# Coolrunner_IO.net
KiCad netlist of a schematic drawn in Altium Designer
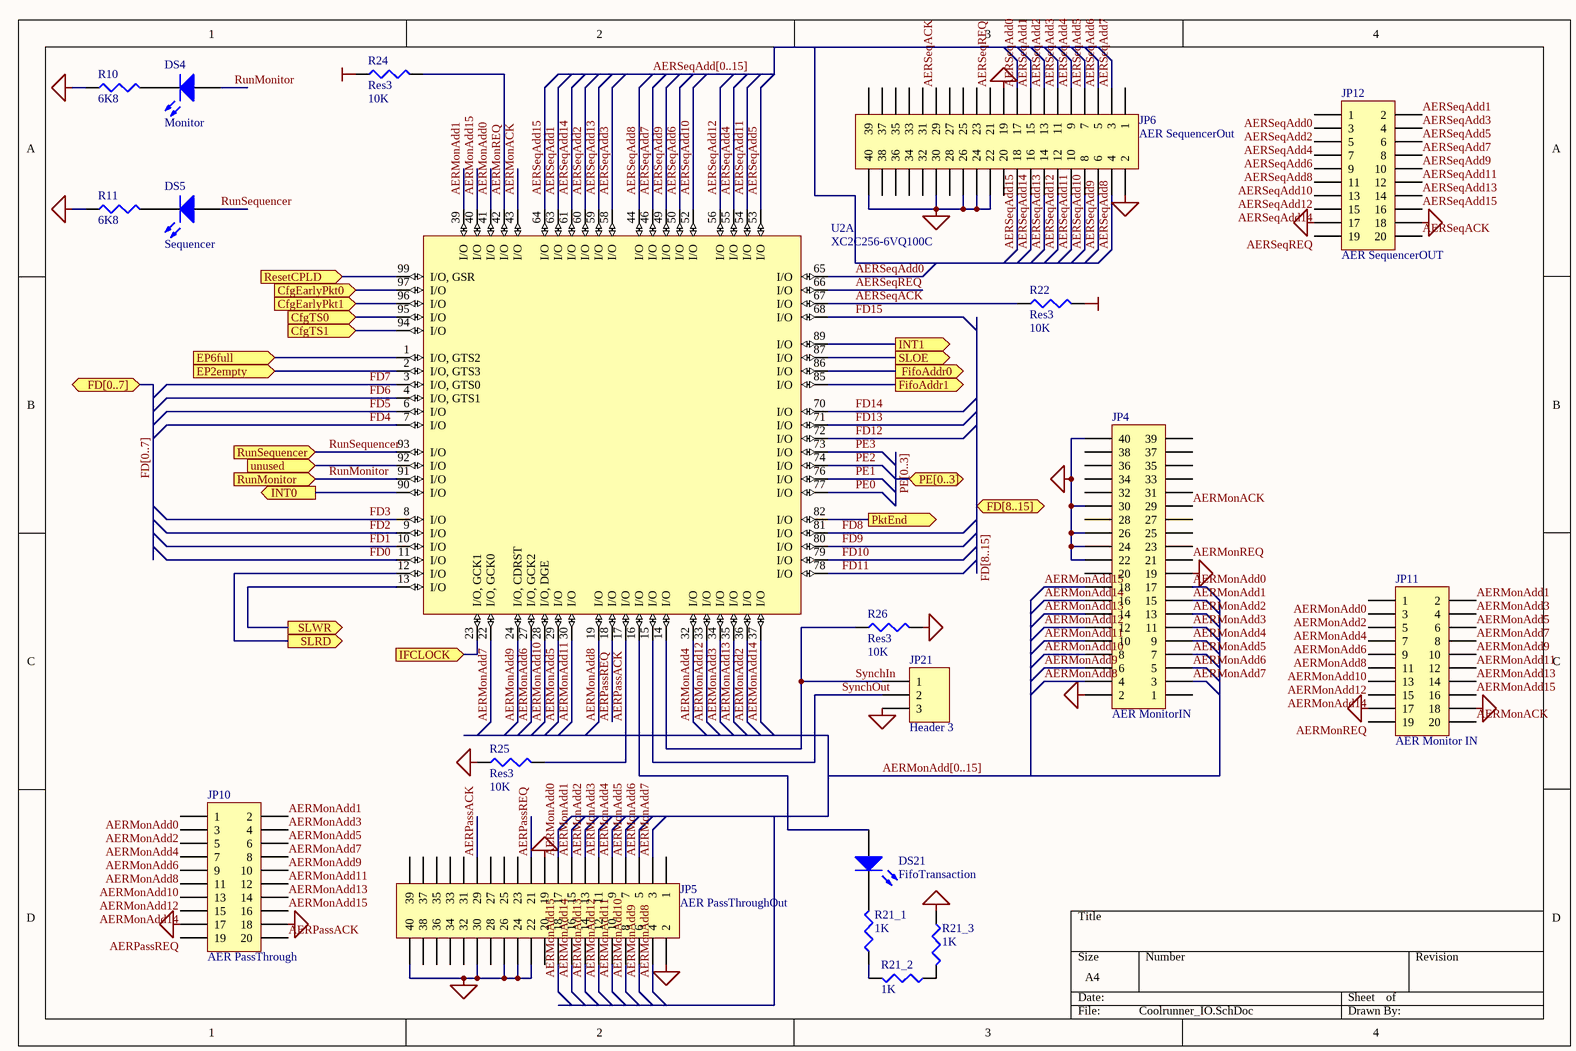
[diagram p0: Coolrunner_IO.SchDoc]

(export (version "E")
  (design (tool "Eeschema 10.0.6"))
  (components
    (comp (ref "DS4")
      (value "Monitor")
      (footprint "LED")
      (description "Typical RED, GREEN, YELLOW, AMBER GaAs LED")
      (fields (field (name "PUBLISHER") "Altium Limited"))
      (libsource (lib "Miscellaneous Devices") (part "LED2"))
    )
    (comp (ref "DS5")
      (value "Sequencer")
      (footprint "LED")
      (description "Typical RED, GREEN, YELLOW, AMBER GaAs LED")
      (fields (field (name "PUBLISHER") "Altium Limited"))
      (libsource (lib "Miscellaneous Devices") (part "LED2"))
    )
    (comp (ref "DS21")
      (value "FifoTransaction")
      (footprint "LED")
      (description "Typical RED, GREEN, YELLOW, AMBER GaAs LED")
      (fields (field (name "PUBLISHER") "Altium Limited"))
      (libsource (lib "Miscellaneous Devices") (part "LED2"))
    )
    (comp (ref "JP4")
      (value "AER MonitorIN")
      (footprint "IDC-40")
      (description "Header, 20-Pin, Dual row")
      (fields (field (name "PUBLISHER") "Altium Limited"))
      (libsource (lib "Miscellaneous Connectors") (part "MHDR2X20"))
    )
    (comp (ref "JP5")
      (value "AER PassThroughOut")
      (footprint "IDC-40")
      (description "Header, 20-Pin, Dual row")
      (fields (field (name "PUBLISHER") "Altium Limited"))
      (libsource (lib "") (part "MHDR2X20_1"))
    )
    (comp (ref "JP6")
      (value "AER SequencerOut")
      (footprint "IDC-40")
      (description "Header, 20-Pin, Dual row")
      (fields (field (name "PUBLISHER") "Altium Limited"))
      (libsource (lib "") (part "MHDR2X20_1"))
    )
    (comp (ref "JP10")
      (value "AER PassThrough")
      (footprint "HDR10x2 w/clips")
      (description "Header, 10-Pin, Dual row")
      (fields (field (name "PUBLISHER") "Altium Limited"))
      (libsource (lib "Miscellaneous Connectors") (part "Header 10X2"))
    )
    (comp (ref "JP11")
      (value "AER Monitor IN")
      (footprint "HDR10x2 w/clips")
      (description "Header, 10-Pin, Dual row")
      (fields (field (name "PUBLISHER") "Altium Limited"))
      (libsource (lib "Miscellaneous Connectors") (part "Header 10X2"))
    )
    (comp (ref "JP12")
      (value "AER SequencerOUT")
      (footprint "HDR10x2 w/clips")
      (description "Header, 10-Pin, Dual row")
      (fields (field (name "PUBLISHER") "Altium Limited"))
      (libsource (lib "Miscellaneous Connectors") (part "Header 10X2"))
    )
    (comp (ref "JP21")
      (value "Header 3")
      (footprint "HDR1X3")
      (description "Header, 3-Pin")
      (fields (field (name "PUBLISHER") "Altium Limited"))
      (libsource (lib "Miscellaneous Connectors") (part "Header 3"))
    )
    (comp (ref "R10")
      (value "6K8")
      (footprint "C1608-0603")
      (description "Resistor")
      (fields (field (name "Comment") "Res3") (field (name "PUBLISHER") "Altium Limited"))
      (libsource (lib "Miscellaneous Devices") (part "Res3"))
    )
    (comp (ref "R11")
      (value "6K8")
      (footprint "C1608-0603")
      (description "Resistor")
      (fields (field (name "Comment") "Res3") (field (name "PUBLISHER") "Altium Limited"))
      (libsource (lib "Miscellaneous Devices") (part "Res3"))
    )
    (comp (ref "R21_1")
      (value "1K")
      (footprint "C1608-0603")
      (description "Resistor")
      (fields (field (name "Comment") "Res3") (field (name "PUBLISHER") "Altium Limited"))
      (libsource (lib "Miscellaneous Devices") (part "Res3"))
    )
    (comp (ref "R21_2")
      (value "1K")
      (footprint "C1608-0603")
      (description "Resistor")
      (fields (field (name "Comment") "Res3") (field (name "PUBLISHER") "Altium Limited"))
      (libsource (lib "Miscellaneous Devices") (part "Res3"))
    )
    (comp (ref "R21_3")
      (value "1K")
      (footprint "C1608-0603")
      (description "Resistor")
      (fields (field (name "Comment") "Res3") (field (name "PUBLISHER") "Altium Limited"))
      (libsource (lib "Miscellaneous Devices") (part "Res3"))
    )
    (comp (ref "R22")
      (value "Res3")
      (footprint "C1608-0603")
      (description "Resistor")
      (fields (field (name "ALTIUM_VALUE") "10K") (field (name "PUBLISHER") "Altium Limited"))
      (libsource (lib "Miscellaneous Devices") (part "Res3"))
    )
    (comp (ref "R24")
      (value "Res3")
      (footprint "C1608-0603")
      (description "Resistor")
      (fields (field (name "ALTIUM_VALUE") "10K") (field (name "PUBLISHER") "Altium Limited"))
      (libsource (lib "Miscellaneous Devices") (part "Res3"))
    )
    (comp (ref "R25")
      (value "Res3")
      (footprint "C1608-0603")
      (description "Resistor")
      (fields (field (name "ALTIUM_VALUE") "10K") (field (name "PUBLISHER") "Altium Limited"))
      (libsource (lib "Miscellaneous Devices") (part "Res3"))
    )
    (comp (ref "R26")
      (value "Res3")
      (footprint "C1608-0603")
      (description "Resistor")
      (fields (field (name "ALTIUM_VALUE") "10K") (field (name "PUBLISHER") "Altium Limited"))
      (libsource (lib "Miscellaneous Devices") (part "Res3"))
    )
    (comp (ref "U2")
      (value "XC2C256-6VQ100C")
      (footprint "VQ100")
      (description "CoolRunner-II, 1.8V, 256 Macrocell CPLD, 100-Pin VQFP, Commercial Grade")
      (fields (field (name "PUBLISHER") "Altium Limited"))
      (libsource (lib "Xilinx CoolRunner II") (part "XC2C256-6VQ100C"))
    )
  )
  (nets
    (net (code "1") (name "/AERMonACK") (class "Default")
      (node (ref "JP11") (pin "20") (pinfunction "20_20") (pintype "passive"))
      (node (ref "JP4") (pin "29") (pinfunction "29_29") (pintype "passive"))
      (node (ref "U2") (pin "43") (pinfunction "I/O_43") (pintype "bidirectional"))
    )
    (net (code "2") (name "/AERMonAdd0") (class "Default")
      (node (ref "JP10") (pin "1") (pinfunction "1_1") (pintype "passive"))
      (node (ref "JP11") (pin "1") (pinfunction "1_1") (pintype "passive"))
      (node (ref "JP4") (pin "17") (pinfunction "17_17") (pintype "passive"))
      (node (ref "JP5") (pin "17") (pinfunction "17_17") (pintype "passive"))
      (node (ref "U2") (pin "41") (pinfunction "I/O_41") (pintype "bidirectional"))
    )
    (net (code "3") (name "/AERMonAdd1") (class "Default")
      (node (ref "JP10") (pin "2") (pinfunction "2_2") (pintype "passive"))
      (node (ref "JP11") (pin "2") (pinfunction "2_2") (pintype "passive"))
      (node (ref "JP4") (pin "15") (pinfunction "15_15") (pintype "passive"))
      (node (ref "JP5") (pin "15") (pinfunction "15_15") (pintype "passive"))
      (node (ref "U2") (pin "39") (pinfunction "I/O_39") (pintype "bidirectional"))
    )
    (net (code "4") (name "/AERMonAdd2") (class "Default")
      (node (ref "JP10") (pin "3") (pinfunction "3_3") (pintype "passive"))
      (node (ref "JP11") (pin "3") (pinfunction "3_3") (pintype "passive"))
      (node (ref "JP4") (pin "13") (pinfunction "13_13") (pintype "passive"))
      (node (ref "JP5") (pin "13") (pinfunction "13_13") (pintype "passive"))
      (node (ref "U2") (pin "36") (pinfunction "I/O_36") (pintype "bidirectional"))
    )
    (net (code "5") (name "/AERMonAdd3") (class "Default")
      (node (ref "JP10") (pin "4") (pinfunction "4_4") (pintype "passive"))
      (node (ref "JP11") (pin "4") (pinfunction "4_4") (pintype "passive"))
      (node (ref "JP4") (pin "11") (pinfunction "11_11") (pintype "passive"))
      (node (ref "JP5") (pin "11") (pinfunction "11_11") (pintype "passive"))
      (node (ref "U2") (pin "34") (pinfunction "I/O_34") (pintype "bidirectional"))
    )
    (net (code "6") (name "/AERMonAdd4") (class "Default")
      (node (ref "JP10") (pin "5") (pinfunction "5_5") (pintype "passive"))
      (node (ref "JP11") (pin "5") (pinfunction "5_5") (pintype "passive"))
      (node (ref "JP4") (pin "9") (pinfunction "9_9") (pintype "passive"))
      (node (ref "JP5") (pin "9") (pinfunction "9_9") (pintype "passive"))
      (node (ref "U2") (pin "32") (pinfunction "I/O_32") (pintype "bidirectional"))
    )
    (net (code "7") (name "/AERMonAdd5") (class "Default")
      (node (ref "JP10") (pin "6") (pinfunction "6_6") (pintype "passive"))
      (node (ref "JP11") (pin "6") (pinfunction "6_6") (pintype "passive"))
      (node (ref "JP4") (pin "7") (pinfunction "7_7") (pintype "passive"))
      (node (ref "JP5") (pin "7") (pinfunction "7_7") (pintype "passive"))
      (node (ref "U2") (pin "29") (pinfunction "I/O_29") (pintype "bidirectional"))
    )
    (net (code "8") (name "/AERMonAdd6") (class "Default")
      (node (ref "JP10") (pin "7") (pinfunction "7_7") (pintype "passive"))
      (node (ref "JP11") (pin "7") (pinfunction "7_7") (pintype "passive"))
      (node (ref "JP4") (pin "5") (pinfunction "5_5") (pintype "passive"))
      (node (ref "JP5") (pin "5") (pinfunction "5_5") (pintype "passive"))
      (node (ref "U2") (pin "27") (pinfunction "I/O,_GCK2_27") (pintype "bidirectional"))
    )
    (net (code "9") (name "/AERMonAdd7") (class "Default")
      (node (ref "JP10") (pin "8") (pinfunction "8_8") (pintype "passive"))
      (node (ref "JP11") (pin "8") (pinfunction "8_8") (pintype "passive"))
      (node (ref "JP4") (pin "3") (pinfunction "3_3") (pintype "passive"))
      (node (ref "JP5") (pin "3") (pinfunction "3_3") (pintype "passive"))
      (node (ref "U2") (pin "22") (pinfunction "I/O,_GCK0_22") (pintype "bidirectional"))
    )
    (net (code "10") (name "/AERMonAdd8") (class "Default")
      (node (ref "JP10") (pin "9") (pinfunction "9_9") (pintype "passive"))
      (node (ref "JP11") (pin "9") (pinfunction "9_9") (pintype "passive"))
      (node (ref "JP4") (pin "4") (pinfunction "4_4") (pintype "passive"))
      (node (ref "JP5") (pin "4") (pinfunction "4_4") (pintype "passive"))
      (node (ref "U2") (pin "19") (pinfunction "I/O_19") (pintype "bidirectional"))
    )
    (net (code "11") (name "/AERMonAdd9") (class "Default")
      (node (ref "JP10") (pin "10") (pinfunction "10_10") (pintype "passive"))
      (node (ref "JP11") (pin "10") (pinfunction "10_10") (pintype "passive"))
      (node (ref "JP4") (pin "6") (pinfunction "6_6") (pintype "passive"))
      (node (ref "JP5") (pin "6") (pinfunction "6_6") (pintype "passive"))
      (node (ref "U2") (pin "24") (pinfunction "I/O,_CDRST_24") (pintype "bidirectional"))
    )
    (net (code "12") (name "/AERMonAdd10") (class "Default")
      (node (ref "JP10") (pin "11") (pinfunction "11_11") (pintype "passive"))
      (node (ref "JP11") (pin "11") (pinfunction "11_11") (pintype "passive"))
      (node (ref "JP4") (pin "8") (pinfunction "8_8") (pintype "passive"))
      (node (ref "JP5") (pin "8") (pinfunction "8_8") (pintype "passive"))
      (node (ref "U2") (pin "28") (pinfunction "I/O,_DGE_28") (pintype "bidirectional"))
    )
    (net (code "13") (name "/AERMonAdd11") (class "Default")
      (node (ref "JP10") (pin "12") (pinfunction "12_12") (pintype "passive"))
      (node (ref "JP11") (pin "12") (pinfunction "12_12") (pintype "passive"))
      (node (ref "JP4") (pin "10") (pinfunction "10_10") (pintype "passive"))
      (node (ref "JP5") (pin "10") (pinfunction "10_10") (pintype "passive"))
      (node (ref "U2") (pin "30") (pinfunction "I/O_30") (pintype "bidirectional"))
    )
    (net (code "14") (name "/AERMonAdd12") (class "Default")
      (node (ref "JP10") (pin "13") (pinfunction "13_13") (pintype "passive"))
      (node (ref "JP11") (pin "13") (pinfunction "13_13") (pintype "passive"))
      (node (ref "JP4") (pin "12") (pinfunction "12_12") (pintype "passive"))
      (node (ref "JP5") (pin "12") (pinfunction "12_12") (pintype "passive"))
      (node (ref "U2") (pin "33") (pinfunction "I/O_33") (pintype "bidirectional"))
    )
    (net (code "15") (name "/AERMonAdd13") (class "Default")
      (node (ref "JP10") (pin "14") (pinfunction "14_14") (pintype "passive"))
      (node (ref "JP11") (pin "14") (pinfunction "14_14") (pintype "passive"))
      (node (ref "JP4") (pin "14") (pinfunction "14_14") (pintype "passive"))
      (node (ref "JP5") (pin "14") (pinfunction "14_14") (pintype "passive"))
      (node (ref "U2") (pin "35") (pinfunction "I/O_35") (pintype "bidirectional"))
    )
    (net (code "16") (name "/AERMonAdd14") (class "Default")
      (node (ref "JP10") (pin "15") (pinfunction "15_15") (pintype "passive"))
      (node (ref "JP11") (pin "15") (pinfunction "15_15") (pintype "passive"))
      (node (ref "JP4") (pin "16") (pinfunction "16_16") (pintype "passive"))
      (node (ref "JP5") (pin "16") (pinfunction "16_16") (pintype "passive"))
      (node (ref "U2") (pin "37") (pinfunction "I/O_37") (pintype "bidirectional"))
    )
    (net (code "17") (name "/AERMonAdd15") (class "Default")
      (node (ref "JP10") (pin "16") (pinfunction "16_16") (pintype "passive"))
      (node (ref "JP11") (pin "16") (pinfunction "16_16") (pintype "passive"))
      (node (ref "JP4") (pin "18") (pinfunction "18_18") (pintype "passive"))
      (node (ref "JP5") (pin "18") (pinfunction "18_18") (pintype "passive"))
      (node (ref "U2") (pin "40") (pinfunction "I/O_40") (pintype "bidirectional"))
    )
    (net (code "19") (name "/AERMonREQ") (class "Default")
      (node (ref "JP11") (pin "19") (pinfunction "19_19") (pintype "passive"))
      (node (ref "JP4") (pin "21") (pinfunction "21_21") (pintype "passive"))
      (node (ref "R24") (pin "2") (pinfunction "2_2") (pintype "passive"))
      (node (ref "U2") (pin "42") (pinfunction "I/O_42") (pintype "bidirectional"))
    )
    (net (code "20") (name "/AERPassACK") (class "Default")
      (node (ref "JP10") (pin "20") (pinfunction "20_20") (pintype "passive"))
      (node (ref "JP5") (pin "29") (pinfunction "29_29") (pintype "passive"))
      (node (ref "R25") (pin "2") (pinfunction "2_2") (pintype "passive"))
      (node (ref "U2") (pin "17") (pinfunction "I/O_17") (pintype "bidirectional"))
    )
    (net (code "21") (name "/AERPassREQ") (class "Default")
      (node (ref "JP10") (pin "19") (pinfunction "19_19") (pintype "passive"))
      (node (ref "JP5") (pin "21") (pinfunction "21_21") (pintype "passive"))
      (node (ref "U2") (pin "18") (pinfunction "I/O_18") (pintype "bidirectional"))
    )
    (net (code "22") (name "/AERSeqACK") (class "Default")
      (node (ref "JP12") (pin "20") (pinfunction "20_20") (pintype "passive"))
      (node (ref "JP6") (pin "29") (pinfunction "29_29") (pintype "passive"))
      (node (ref "R22") (pin "1") (pinfunction "1_1") (pintype "passive"))
      (node (ref "U2") (pin "67") (pinfunction "I/O_67") (pintype "bidirectional"))
    )
    (net (code "23") (name "/AERSeqAdd0") (class "Default")
      (node (ref "JP12") (pin "1") (pinfunction "1_1") (pintype "passive"))
      (node (ref "JP6") (pin "17") (pinfunction "17_17") (pintype "passive"))
      (node (ref "U2") (pin "65") (pinfunction "I/O_65") (pintype "bidirectional"))
    )
    (net (code "24") (name "/AERSeqAdd1") (class "Default")
      (node (ref "JP12") (pin "2") (pinfunction "2_2") (pintype "passive"))
      (node (ref "JP6") (pin "15") (pinfunction "15_15") (pintype "passive"))
      (node (ref "U2") (pin "63") (pinfunction "I/O_63") (pintype "bidirectional"))
    )
    (net (code "25") (name "/AERSeqAdd2") (class "Default")
      (node (ref "JP12") (pin "3") (pinfunction "3_3") (pintype "passive"))
      (node (ref "JP6") (pin "13") (pinfunction "13_13") (pintype "passive"))
      (node (ref "U2") (pin "60") (pinfunction "I/O_60") (pintype "bidirectional"))
    )
    (net (code "26") (name "/AERSeqAdd3") (class "Default")
      (node (ref "JP12") (pin "4") (pinfunction "4_4") (pintype "passive"))
      (node (ref "JP6") (pin "11") (pinfunction "11_11") (pintype "passive"))
      (node (ref "U2") (pin "58") (pinfunction "I/O_58") (pintype "bidirectional"))
    )
    (net (code "27") (name "/AERSeqAdd4") (class "Default")
      (node (ref "JP12") (pin "5") (pinfunction "5_5") (pintype "passive"))
      (node (ref "JP6") (pin "9") (pinfunction "9_9") (pintype "passive"))
      (node (ref "U2") (pin "55") (pinfunction "I/O_55") (pintype "bidirectional"))
    )
    (net (code "28") (name "/AERSeqAdd5") (class "Default")
      (node (ref "JP12") (pin "6") (pinfunction "6_6") (pintype "passive"))
      (node (ref "JP6") (pin "7") (pinfunction "7_7") (pintype "passive"))
      (node (ref "U2") (pin "53") (pinfunction "I/O_53") (pintype "bidirectional"))
    )
    (net (code "29") (name "/AERSeqAdd6") (class "Default")
      (node (ref "JP12") (pin "7") (pinfunction "7_7") (pintype "passive"))
      (node (ref "JP6") (pin "5") (pinfunction "5_5") (pintype "passive"))
      (node (ref "U2") (pin "50") (pinfunction "I/O_50") (pintype "bidirectional"))
    )
    (net (code "30") (name "/AERSeqAdd7") (class "Default")
      (node (ref "JP12") (pin "8") (pinfunction "8_8") (pintype "passive"))
      (node (ref "JP6") (pin "3") (pinfunction "3_3") (pintype "passive"))
      (node (ref "U2") (pin "46") (pinfunction "I/O_46") (pintype "bidirectional"))
    )
    (net (code "31") (name "/AERSeqAdd8") (class "Default")
      (node (ref "JP12") (pin "9") (pinfunction "9_9") (pintype "passive"))
      (node (ref "JP6") (pin "4") (pinfunction "4_4") (pintype "passive"))
      (node (ref "U2") (pin "44") (pinfunction "I/O_44") (pintype "bidirectional"))
    )
    (net (code "32") (name "/AERSeqAdd9") (class "Default")
      (node (ref "JP12") (pin "10") (pinfunction "10_10") (pintype "passive"))
      (node (ref "JP6") (pin "6") (pinfunction "6_6") (pintype "passive"))
      (node (ref "U2") (pin "49") (pinfunction "I/O_49") (pintype "bidirectional"))
    )
    (net (code "33") (name "/AERSeqAdd10") (class "Default")
      (node (ref "JP12") (pin "11") (pinfunction "11_11") (pintype "passive"))
      (node (ref "JP6") (pin "8") (pinfunction "8_8") (pintype "passive"))
      (node (ref "U2") (pin "52") (pinfunction "I/O_52") (pintype "bidirectional"))
    )
    (net (code "34") (name "/AERSeqAdd11") (class "Default")
      (node (ref "JP12") (pin "12") (pinfunction "12_12") (pintype "passive"))
      (node (ref "JP6") (pin "10") (pinfunction "10_10") (pintype "passive"))
      (node (ref "U2") (pin "54") (pinfunction "I/O_54") (pintype "bidirectional"))
    )
    (net (code "35") (name "/AERSeqAdd12") (class "Default")
      (node (ref "JP12") (pin "13") (pinfunction "13_13") (pintype "passive"))
      (node (ref "JP6") (pin "12") (pinfunction "12_12") (pintype "passive"))
      (node (ref "U2") (pin "56") (pinfunction "I/O_56") (pintype "bidirectional"))
    )
    (net (code "36") (name "/AERSeqAdd13") (class "Default")
      (node (ref "JP12") (pin "14") (pinfunction "14_14") (pintype "passive"))
      (node (ref "JP6") (pin "14") (pinfunction "14_14") (pintype "passive"))
      (node (ref "U2") (pin "59") (pinfunction "I/O_59") (pintype "bidirectional"))
    )
    (net (code "37") (name "/AERSeqAdd14") (class "Default")
      (node (ref "JP12") (pin "15") (pinfunction "15_15") (pintype "passive"))
      (node (ref "JP6") (pin "16") (pinfunction "16_16") (pintype "passive"))
      (node (ref "U2") (pin "61") (pinfunction "I/O_61") (pintype "bidirectional"))
    )
    (net (code "38") (name "/AERSeqAdd15") (class "Default")
      (node (ref "JP12") (pin "16") (pinfunction "16_16") (pintype "passive"))
      (node (ref "JP6") (pin "18") (pinfunction "18_18") (pintype "passive"))
      (node (ref "U2") (pin "64") (pinfunction "I/O_64") (pintype "bidirectional"))
    )
    (net (code "40") (name "/AERSeqREQ") (class "Default")
      (node (ref "JP12") (pin "19") (pinfunction "19_19") (pintype "passive"))
      (node (ref "JP6") (pin "21") (pinfunction "21_21") (pintype "passive"))
      (node (ref "U2") (pin "66") (pinfunction "I/O_66") (pintype "bidirectional"))
    )
    (net (code "41") (name "/CfgEarlyPkt0") (class "Default")
      (node (ref "U2") (pin "97") (pinfunction "I/O_97") (pintype "bidirectional"))
    )
    (net (code "42") (name "/CfgEarlyPkt1") (class "Default")
      (node (ref "U2") (pin "96") (pinfunction "I/O_96") (pintype "bidirectional"))
    )
    (net (code "43") (name "/CfgTS0") (class "Default")
      (node (ref "U2") (pin "95") (pinfunction "I/O_95") (pintype "bidirectional"))
    )
    (net (code "44") (name "/CfgTS1") (class "Default")
      (node (ref "U2") (pin "94") (pinfunction "I/O_94") (pintype "bidirectional"))
    )
    (net (code "45") (name "/EP2empty") (class "Default")
      (node (ref "U2") (pin "2") (pinfunction "I/O,_GTS3_2") (pintype "bidirectional"))
    )
    (net (code "46") (name "/EP6full") (class "Default")
      (node (ref "U2") (pin "1") (pinfunction "I/O,_GTS2_1") (pintype "bidirectional"))
    )
    (net (code "47") (name "/FD0") (class "Default")
      (node (ref "U2") (pin "11") (pinfunction "I/O_11") (pintype "bidirectional"))
    )
    (net (code "48") (name "/FD1") (class "Default")
      (node (ref "U2") (pin "10") (pinfunction "I/O_10") (pintype "bidirectional"))
    )
    (net (code "49") (name "/FD2") (class "Default")
      (node (ref "U2") (pin "9") (pinfunction "I/O_9") (pintype "bidirectional"))
    )
    (net (code "50") (name "/FD3") (class "Default")
      (node (ref "U2") (pin "8") (pinfunction "I/O_8") (pintype "bidirectional"))
    )
    (net (code "51") (name "/FD4") (class "Default")
      (node (ref "U2") (pin "7") (pinfunction "I/O_7") (pintype "bidirectional"))
    )
    (net (code "52") (name "/FD5") (class "Default")
      (node (ref "U2") (pin "6") (pinfunction "I/O_6") (pintype "bidirectional"))
    )
    (net (code "53") (name "/FD6") (class "Default")
      (node (ref "U2") (pin "4") (pinfunction "I/O,_GTS1_4") (pintype "bidirectional"))
    )
    (net (code "54") (name "/FD7") (class "Default")
      (node (ref "U2") (pin "3") (pinfunction "I/O,_GTS0_3") (pintype "bidirectional"))
    )
    (net (code "55") (name "/FD8") (class "Default")
      (node (ref "U2") (pin "81") (pinfunction "I/O_81") (pintype "bidirectional"))
    )
    (net (code "56") (name "/FD9") (class "Default")
      (node (ref "U2") (pin "80") (pinfunction "I/O_80") (pintype "bidirectional"))
    )
    (net (code "57") (name "/FD10") (class "Default")
      (node (ref "U2") (pin "79") (pinfunction "I/O_79") (pintype "bidirectional"))
    )
    (net (code "58") (name "/FD11") (class "Default")
      (node (ref "U2") (pin "78") (pinfunction "I/O_78") (pintype "bidirectional"))
    )
    (net (code "59") (name "/FD12") (class "Default")
      (node (ref "U2") (pin "72") (pinfunction "I/O_72") (pintype "bidirectional"))
    )
    (net (code "60") (name "/FD13") (class "Default")
      (node (ref "U2") (pin "71") (pinfunction "I/O_71") (pintype "bidirectional"))
    )
    (net (code "61") (name "/FD14") (class "Default")
      (node (ref "U2") (pin "70") (pinfunction "I/O_70") (pintype "bidirectional"))
    )
    (net (code "62") (name "/FD15") (class "Default")
      (node (ref "U2") (pin "68") (pinfunction "I/O_68") (pintype "bidirectional"))
    )
    (net (code "65") (name "/FifoAddr0") (class "Default")
      (node (ref "U2") (pin "86") (pinfunction "I/O_86") (pintype "bidirectional"))
    )
    (net (code "66") (name "/FifoAddr1") (class "Default")
      (node (ref "U2") (pin "85") (pinfunction "I/O_85") (pintype "bidirectional"))
    )
    (net (code "67") (name "/IFCLOCK") (class "Default")
      (node (ref "U2") (pin "23") (pinfunction "I/O,_GCK1_23") (pintype "bidirectional"))
    )
    (net (code "68") (name "/INT0") (class "Default")
      (node (ref "U2") (pin "90") (pinfunction "I/O_90") (pintype "bidirectional"))
    )
    (net (code "69") (name "/INT1") (class "Default")
      (node (ref "U2") (pin "89") (pinfunction "I/O_89") (pintype "bidirectional"))
    )
    (net (code "70") (name "/PE0") (class "Default")
      (node (ref "U2") (pin "77") (pinfunction "I/O_77") (pintype "bidirectional"))
    )
    (net (code "71") (name "/PE1") (class "Default")
      (node (ref "U2") (pin "76") (pinfunction "I/O_76") (pintype "bidirectional"))
    )
    (net (code "72") (name "/PE2") (class "Default")
      (node (ref "U2") (pin "74") (pinfunction "I/O_74") (pintype "bidirectional"))
    )
    (net (code "73") (name "/PE3") (class "Default")
      (node (ref "U2") (pin "73") (pinfunction "I/O_73") (pintype "bidirectional"))
    )
    (net (code "75") (name "/PktEnd") (class "Default")
      (node (ref "U2") (pin "82") (pinfunction "I/O_82") (pintype "bidirectional"))
    )
    (net (code "76") (name "/ResetCPLD") (class "Default")
      (node (ref "U2") (pin "99") (pinfunction "I/O,_GSR_99") (pintype "bidirectional"))
    )
    (net (code "77") (name "/RunMonitor") (class "Default")
      (node (ref "DS4") (pin "1") (pinfunction "A_1") (pintype "passive"))
      (node (ref "U2") (pin "91") (pinfunction "I/O_91") (pintype "bidirectional"))
    )
    (net (code "78") (name "/RunSequencer") (class "Default")
      (node (ref "DS5") (pin "1") (pinfunction "A_1") (pintype "passive"))
      (node (ref "U2") (pin "93") (pinfunction "I/O_93") (pintype "bidirectional"))
    )
    (net (code "79") (name "/SLOE") (class "Default")
      (node (ref "U2") (pin "87") (pinfunction "I/O_87") (pintype "bidirectional"))
    )
    (net (code "80") (name "/SLRD") (class "Default")
      (node (ref "U2") (pin "12") (pinfunction "I/O_12") (pintype "bidirectional"))
    )
    (net (code "81") (name "/SLWR") (class "Default")
      (node (ref "U2") (pin "13") (pinfunction "I/O_13") (pintype "bidirectional"))
    )
    (net (code "82") (name "/SynchIn") (class "Default")
      (node (ref "JP21") (pin "1") (pinfunction "1_1") (pintype "passive"))
      (node (ref "R26") (pin "1") (pinfunction "1_1") (pintype "passive"))
      (node (ref "U2") (pin "14") (pinfunction "I/O_14") (pintype "bidirectional"))
    )
    (net (code "83") (name "/SynchOut") (class "Default")
      (node (ref "JP21") (pin "2") (pinfunction "2_2") (pintype "passive"))
      (node (ref "U2") (pin "15") (pinfunction "I/O_15") (pintype "bidirectional"))
    )
    (net (code "84") (name "/unused") (class "Default")
      (node (ref "U2") (pin "92") (pinfunction "I/O_92") (pintype "bidirectional"))
    )
    (net (code "85") (name "3.3V") (class "Default")
      (node (ref "R22") (pin "2") (pinfunction "2_2") (pintype "passive"))
      (node (ref "R24") (pin "1") (pinfunction "1_1") (pintype "passive"))
    )
    (net (code "86") (name "GND") (class "Default")
      (node (ref "JP10") (pin "17") (pinfunction "17_17") (pintype "passive"))
      (node (ref "JP10") (pin "18") (pinfunction "18_18") (pintype "passive"))
      (node (ref "JP11") (pin "17") (pinfunction "17_17") (pintype "passive"))
      (node (ref "JP11") (pin "18") (pinfunction "18_18") (pintype "passive"))
      (node (ref "JP12") (pin "17") (pinfunction "17_17") (pintype "passive"))
      (node (ref "JP12") (pin "18") (pinfunction "18_18") (pintype "passive"))
      (node (ref "JP21") (pin "3") (pinfunction "3_3") (pintype "passive"))
      (node (ref "JP4") (pin "19") (pinfunction "19_19") (pintype "passive"))
      (node (ref "JP4") (pin "2") (pinfunction "2_2") (pintype "passive"))
      (node (ref "JP4") (pin "22") (pinfunction "22_22") (pintype "passive"))
      (node (ref "JP4") (pin "24") (pinfunction "24_24") (pintype "passive"))
      (node (ref "JP4") (pin "26") (pinfunction "26_26") (pintype "passive"))
      (node (ref "JP4") (pin "30") (pinfunction "30_30") (pintype "passive"))
      (node (ref "JP4") (pin "40") (pinfunction "40_40") (pintype "passive"))
      (node (ref "JP5") (pin "19") (pinfunction "19_19") (pintype "passive"))
      (node (ref "JP5") (pin "2") (pinfunction "2_2") (pintype "passive"))
      (node (ref "JP5") (pin "22") (pinfunction "22_22") (pintype "passive"))
      (node (ref "JP5") (pin "24") (pinfunction "24_24") (pintype "passive"))
      (node (ref "JP5") (pin "26") (pinfunction "26_26") (pintype "passive"))
      (node (ref "JP5") (pin "30") (pinfunction "30_30") (pintype "passive"))
      (node (ref "JP5") (pin "40") (pinfunction "40_40") (pintype "passive"))
      (node (ref "JP6") (pin "19") (pinfunction "19_19") (pintype "passive"))
      (node (ref "JP6") (pin "2") (pinfunction "2_2") (pintype "passive"))
      (node (ref "JP6") (pin "22") (pinfunction "22_22") (pintype "passive"))
      (node (ref "JP6") (pin "24") (pinfunction "24_24") (pintype "passive"))
      (node (ref "JP6") (pin "26") (pinfunction "26_26") (pintype "passive"))
      (node (ref "JP6") (pin "30") (pinfunction "30_30") (pintype "passive"))
      (node (ref "JP6") (pin "40") (pinfunction "40_40") (pintype "passive"))
      (node (ref "R10") (pin "1") (pinfunction "1_1") (pintype "passive"))
      (node (ref "R11") (pin "1") (pinfunction "1_1") (pintype "passive"))
      (node (ref "R21_3") (pin "1") (pinfunction "1_1") (pintype "passive"))
      (node (ref "R25") (pin "1") (pinfunction "1_1") (pintype "passive"))
      (node (ref "R26") (pin "2") (pinfunction "2_2") (pintype "passive"))
    )
    (net (code "87") (name "Net-(DS4-K)") (class "Default")
      (node (ref "DS4") (pin "2") (pinfunction "K_2") (pintype "passive"))
      (node (ref "R10") (pin "2") (pinfunction "2_2") (pintype "passive"))
    )
    (net (code "88") (name "Net-(DS5-K)") (class "Default")
      (node (ref "DS5") (pin "2") (pinfunction "K_2") (pintype "passive"))
      (node (ref "R11") (pin "2") (pinfunction "2_2") (pintype "passive"))
    )
    (net (code "89") (name "Net-(DS21-A)") (class "Default")
      (node (ref "DS21") (pin "1") (pinfunction "A_1") (pintype "passive"))
      (node (ref "U2") (pin "16") (pinfunction "I/O_16") (pintype "bidirectional"))
    )
    (net (code "90") (name "Net-(DS21-K)") (class "Default")
      (node (ref "DS21") (pin "2") (pinfunction "K_2") (pintype "passive"))
      (node (ref "R21_1") (pin "2") (pinfunction "2_2") (pintype "passive"))
    )
    (net (code "91") (name "Net-(R21_1-Pad1)") (class "Default")
      (node (ref "R21_1") (pin "1") (pinfunction "1_1") (pintype "passive"))
      (node (ref "R21_2") (pin "2") (pinfunction "2_2") (pintype "passive"))
    )
    (net (code "92") (name "Net-(R21_2-Pad1)") (class "Default")
      (node (ref "R21_2") (pin "1") (pinfunction "1_1") (pintype "passive"))
      (node (ref "R21_3") (pin "2") (pinfunction "2_2") (pintype "passive"))
    )
    (net (code "93") (name "unconnected-(JP4-Pad1)") (class "Default")
      (node (ref "JP4") (pin "1") (pinfunction "1_1") (pintype "passive"))
    )
    (net (code "94") (name "unconnected-(JP4-Pad20)") (class "Default")
      (node (ref "JP4") (pin "20") (pinfunction "20_20") (pintype "passive"))
    )
    (net (code "95") (name "unconnected-(JP4-Pad23)") (class "Default")
      (node (ref "JP4") (pin "23") (pinfunction "23_23") (pintype "passive"))
    )
    (net (code "96") (name "unconnected-(JP4-Pad25)") (class "Default")
      (node (ref "JP4") (pin "25") (pinfunction "25_25") (pintype "passive"))
    )
    (net (code "97") (name "unconnected-(JP4-Pad27)") (class "Default")
      (node (ref "JP4") (pin "27") (pinfunction "27_27") (pintype "passive"))
    )
    (net (code "98") (name "unconnected-(JP4-Pad28)") (class "Default")
      (node (ref "JP4") (pin "28") (pinfunction "28_28") (pintype "passive"))
    )
    (net (code "99") (name "unconnected-(JP4-Pad31)") (class "Default")
      (node (ref "JP4") (pin "31") (pinfunction "31_31") (pintype "passive"))
    )
    (net (code "100") (name "unconnected-(JP4-Pad32)") (class "Default")
      (node (ref "JP4") (pin "32") (pinfunction "32_32") (pintype "passive"))
    )
    (net (code "101") (name "unconnected-(JP4-Pad33)") (class "Default")
      (node (ref "JP4") (pin "33") (pinfunction "33_33") (pintype "passive"))
    )
    (net (code "102") (name "unconnected-(JP4-Pad34)") (class "Default")
      (node (ref "JP4") (pin "34") (pinfunction "34_34") (pintype "passive"))
    )
    (net (code "103") (name "unconnected-(JP4-Pad35)") (class "Default")
      (node (ref "JP4") (pin "35") (pinfunction "35_35") (pintype "passive"))
    )
    (net (code "104") (name "unconnected-(JP4-Pad36)") (class "Default")
      (node (ref "JP4") (pin "36") (pinfunction "36_36") (pintype "passive"))
    )
    (net (code "105") (name "unconnected-(JP4-Pad37)") (class "Default")
      (node (ref "JP4") (pin "37") (pinfunction "37_37") (pintype "passive"))
    )
    (net (code "106") (name "unconnected-(JP4-Pad38)") (class "Default")
      (node (ref "JP4") (pin "38") (pinfunction "38_38") (pintype "passive"))
    )
    (net (code "107") (name "unconnected-(JP4-Pad39)") (class "Default")
      (node (ref "JP4") (pin "39") (pinfunction "39_39") (pintype "passive"))
    )
    (net (code "108") (name "unconnected-(JP5-Pad1)") (class "Default")
      (node (ref "JP5") (pin "1") (pinfunction "1_1") (pintype "passive"))
    )
    (net (code "109") (name "unconnected-(JP5-Pad20)") (class "Default")
      (node (ref "JP5") (pin "20") (pinfunction "20_20") (pintype "passive"))
    )
    (net (code "110") (name "unconnected-(JP5-Pad23)") (class "Default")
      (node (ref "JP5") (pin "23") (pinfunction "23_23") (pintype "passive"))
    )
    (net (code "111") (name "unconnected-(JP5-Pad25)") (class "Default")
      (node (ref "JP5") (pin "25") (pinfunction "25_25") (pintype "passive"))
    )
    (net (code "112") (name "unconnected-(JP5-Pad27)") (class "Default")
      (node (ref "JP5") (pin "27") (pinfunction "27_27") (pintype "passive"))
    )
    (net (code "113") (name "unconnected-(JP5-Pad28)") (class "Default")
      (node (ref "JP5") (pin "28") (pinfunction "28_28") (pintype "passive"))
    )
    (net (code "114") (name "unconnected-(JP5-Pad31)") (class "Default")
      (node (ref "JP5") (pin "31") (pinfunction "31_31") (pintype "passive"))
    )
    (net (code "115") (name "unconnected-(JP5-Pad32)") (class "Default")
      (node (ref "JP5") (pin "32") (pinfunction "32_32") (pintype "passive"))
    )
    (net (code "116") (name "unconnected-(JP5-Pad33)") (class "Default")
      (node (ref "JP5") (pin "33") (pinfunction "33_33") (pintype "passive"))
    )
    (net (code "117") (name "unconnected-(JP5-Pad34)") (class "Default")
      (node (ref "JP5") (pin "34") (pinfunction "34_34") (pintype "passive"))
    )
    (net (code "118") (name "unconnected-(JP5-Pad35)") (class "Default")
      (node (ref "JP5") (pin "35") (pinfunction "35_35") (pintype "passive"))
    )
    (net (code "119") (name "unconnected-(JP5-Pad36)") (class "Default")
      (node (ref "JP5") (pin "36") (pinfunction "36_36") (pintype "passive"))
    )
    (net (code "120") (name "unconnected-(JP5-Pad37)") (class "Default")
      (node (ref "JP5") (pin "37") (pinfunction "37_37") (pintype "passive"))
    )
    (net (code "121") (name "unconnected-(JP5-Pad38)") (class "Default")
      (node (ref "JP5") (pin "38") (pinfunction "38_38") (pintype "passive"))
    )
    (net (code "122") (name "unconnected-(JP5-Pad39)") (class "Default")
      (node (ref "JP5") (pin "39") (pinfunction "39_39") (pintype "passive"))
    )
    (net (code "123") (name "unconnected-(JP6-Pad1)") (class "Default")
      (node (ref "JP6") (pin "1") (pinfunction "1_1") (pintype "passive"))
    )
    (net (code "124") (name "unconnected-(JP6-Pad20)") (class "Default")
      (node (ref "JP6") (pin "20") (pinfunction "20_20") (pintype "passive"))
    )
    (net (code "125") (name "unconnected-(JP6-Pad23)") (class "Default")
      (node (ref "JP6") (pin "23") (pinfunction "23_23") (pintype "passive"))
    )
    (net (code "126") (name "unconnected-(JP6-Pad25)") (class "Default")
      (node (ref "JP6") (pin "25") (pinfunction "25_25") (pintype "passive"))
    )
    (net (code "127") (name "unconnected-(JP6-Pad27)") (class "Default")
      (node (ref "JP6") (pin "27") (pinfunction "27_27") (pintype "passive"))
    )
    (net (code "128") (name "unconnected-(JP6-Pad28)") (class "Default")
      (node (ref "JP6") (pin "28") (pinfunction "28_28") (pintype "passive"))
    )
    (net (code "129") (name "unconnected-(JP6-Pad31)") (class "Default")
      (node (ref "JP6") (pin "31") (pinfunction "31_31") (pintype "passive"))
    )
    (net (code "130") (name "unconnected-(JP6-Pad32)") (class "Default")
      (node (ref "JP6") (pin "32") (pinfunction "32_32") (pintype "passive"))
    )
    (net (code "131") (name "unconnected-(JP6-Pad33)") (class "Default")
      (node (ref "JP6") (pin "33") (pinfunction "33_33") (pintype "passive"))
    )
    (net (code "132") (name "unconnected-(JP6-Pad34)") (class "Default")
      (node (ref "JP6") (pin "34") (pinfunction "34_34") (pintype "passive"))
    )
    (net (code "133") (name "unconnected-(JP6-Pad35)") (class "Default")
      (node (ref "JP6") (pin "35") (pinfunction "35_35") (pintype "passive"))
    )
    (net (code "134") (name "unconnected-(JP6-Pad36)") (class "Default")
      (node (ref "JP6") (pin "36") (pinfunction "36_36") (pintype "passive"))
    )
    (net (code "135") (name "unconnected-(JP6-Pad37)") (class "Default")
      (node (ref "JP6") (pin "37") (pinfunction "37_37") (pintype "passive"))
    )
    (net (code "136") (name "unconnected-(JP6-Pad38)") (class "Default")
      (node (ref "JP6") (pin "38") (pinfunction "38_38") (pintype "passive"))
    )
    (net (code "137") (name "unconnected-(JP6-Pad39)") (class "Default")
      (node (ref "JP6") (pin "39") (pinfunction "39_39") (pintype "passive"))
    )
  )
)
